# driver_bridge.net
KiCad netlist of a schematic drawn in Altium Designer
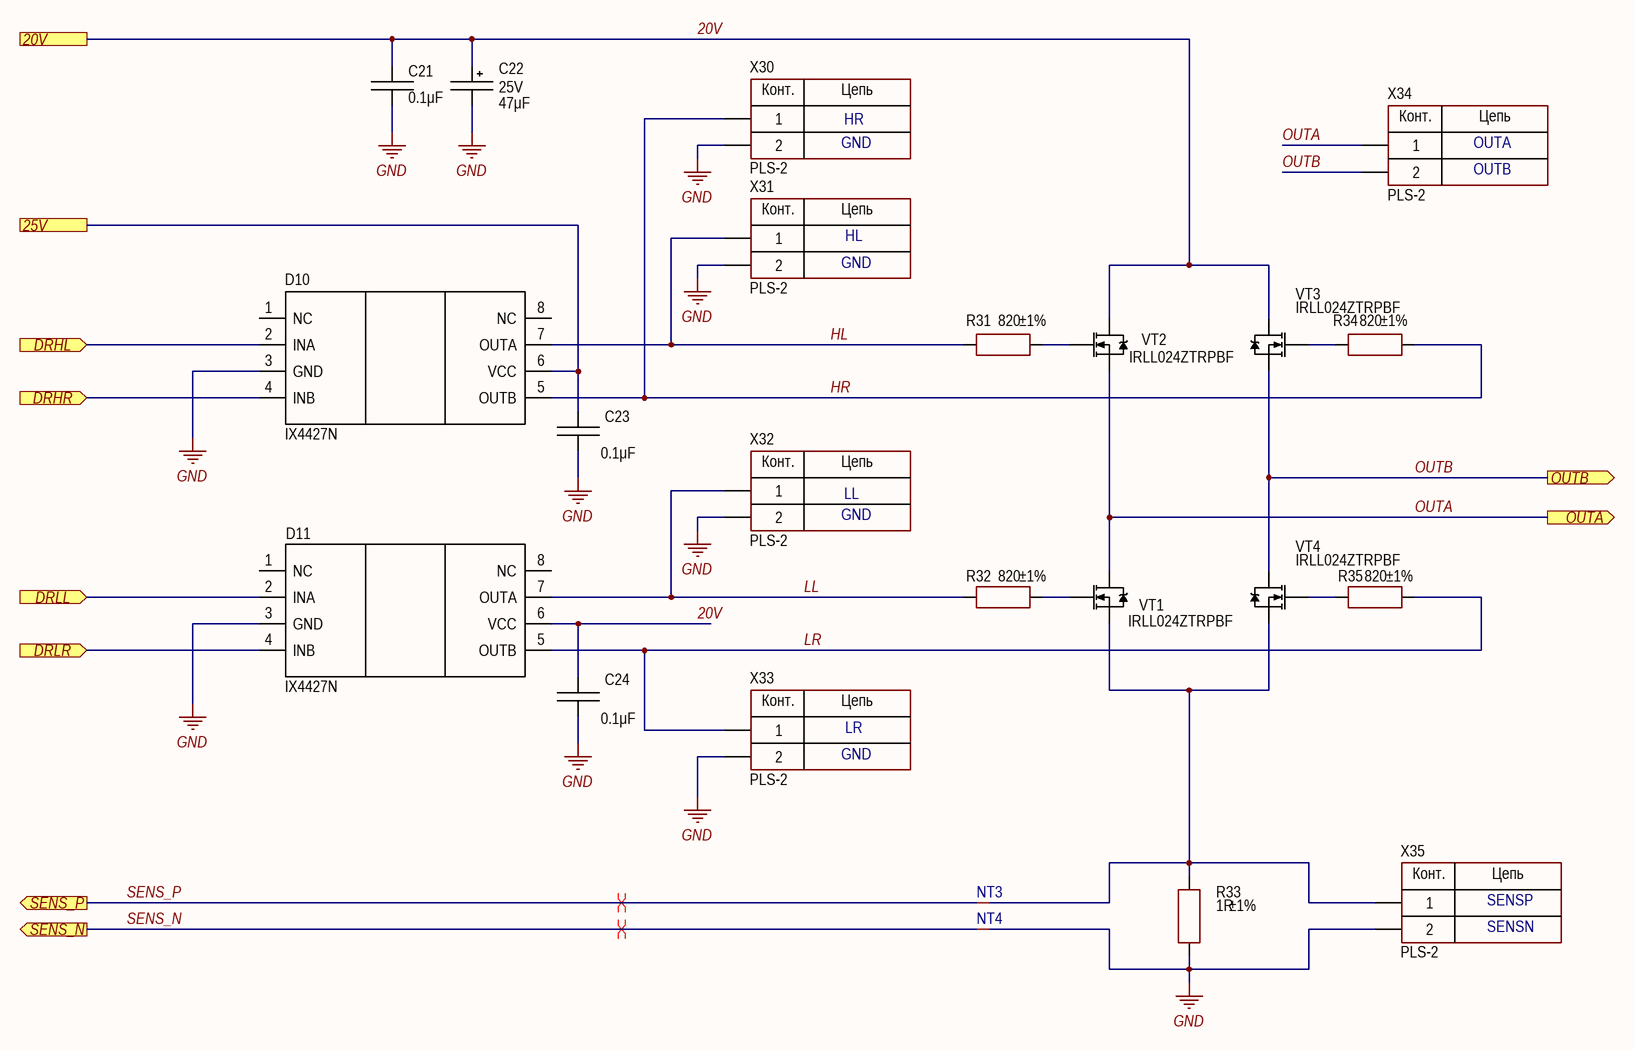
[diagram p0: driver_bridge.SchDoc]

(export (version "E")
  (design (tool "Eeschema 10.0.6"))
  (components
    (comp (ref "C21")
      (value "0.1μF")
      (footprint "CAP: 1206")
      (fields
        (field (name "MANUFACTURER") "Murata Electronics")
        (field (name "PARTNUMBER") "GRM319R71H104K")
        (field (name "VALUEMANUFACTURERPARTNUMBER") "Ceramic capacitor, 0.1μF, X7R, ±10%, 50V, 1206, -55...+125°C")
      )
      (libsource (lib "capacitor") (part "Ceramic_1206"))
    )
    (comp (ref "C22")
      (value "47μF")
      (footprint "CAP: D6.3C2.5H11")
      (fields
        (field (name "MANUFACTURER") "Wurth")
        (field (name "PARTNUMBER") "860080475013")
        (field (name "VALUEMANUFACTURERPARTNUMBER") "Aluminium capacitor, 47μF, 25V, ±20%, 54mOhm, 14x10x5 mm, -55...+105°C")
        (field (name "VOLTAGE") "25V")
      )
      (libsource (lib "capacitor") (part "Aluminium"))
    )
    (comp (ref "C23")
      (value "0.1μF")
      (footprint "CAP: 1206")
      (fields
        (field (name "MANUFACTURER") "Murata Electronics")
        (field (name "PARTNUMBER") "GRM319R71H104K")
        (field (name "VALUEMANUFACTURERPARTNUMBER") "Ceramic capacitor, 0.1μF, X7R, ±10%, 50V, 1206, -55...+125°C")
      )
      (libsource (lib "capacitor") (part "Ceramic_1206"))
    )
    (comp (ref "C24")
      (value "0.1μF")
      (footprint "CAP: 1206")
      (fields
        (field (name "MANUFACTURER") "Murata Electronics")
        (field (name "PARTNUMBER") "GRM319R71H104K")
        (field (name "VALUEMANUFACTURERPARTNUMBER") "Ceramic capacitor, 0.1μF, X7R, ±10%, 50V, 1206, -55...+125°C")
      )
      (libsource (lib "capacitor") (part "Ceramic_1206"))
    )
    (comp (ref "D10")
      (value "Ixys Corporation")
      (footprint "8-SOIC")
      (description "Gate driver")
      (fields (field (name "PARTNUMBER") "IX4427N"))
      (libsource (lib "ic-gate-driver") (part "IX4427N"))
    )
    (comp (ref "D11")
      (value "Ixys Corporation")
      (footprint "8-SOIC")
      (description "Gate driver")
      (fields (field (name "PARTNUMBER") "IX4427N"))
      (libsource (lib "ic-gate-driver") (part "IX4427N"))
    )
    (comp (ref "NT3")
      (value "Net_Tie")
      (footprint "NET TIE 0.5_1.5")
      (libsource (lib "other") (part "Net_Tie"))
    )
    (comp (ref "NT4")
      (value "Net_Tie")
      (footprint "NET TIE 0.5_1.5")
      (libsource (lib "other") (part "Net_Tie"))
    )
    (comp (ref "R31")
      (value "820")
      (footprint "RES: 1206")
      (fields
        (field (name "MANUFACTURER") "Yageo")
        (field (name "PARTNUMBER") "RC1206JR-07100RL")
        (field (name "VALUEMANUFACTURERPARTNUMBER") "Resistor film, 820, ±1%, 1206, 0.25W, -55...+125°C")
        (field (name "TOLERANCE") "±1%")
      )
      (libsource (lib "resistor") (part "Resistor_1206"))
    )
    (comp (ref "R32")
      (value "820")
      (footprint "RES: 1206")
      (fields
        (field (name "MANUFACTURER") "Yageo")
        (field (name "PARTNUMBER") "RC1206JR-07100RL")
        (field (name "VALUEMANUFACTURERPARTNUMBER") "Resistor film, 820, ±1%, 1206, 0.25W, -55...+125°C")
        (field (name "TOLERANCE") "±1%")
      )
      (libsource (lib "resistor") (part "Resistor_1206"))
    )
    (comp (ref "R33")
      (value "1R")
      (footprint "RES: 2512")
      (fields
        (field (name "MANUFACTURER") "Yageo")
        (field (name "PARTNUMBER") "RC2512JK-07100RL")
        (field (name "VALUEMANUFACTURERPARTNUMBER") "Resistor film, 1R, ±1%, 2512, 1W, -55...+125°C")
        (field (name "TOLERANCE") "±1%")
      )
      (libsource (lib "resistor") (part "Resistor_2512"))
    )
    (comp (ref "R34")
      (value "820")
      (footprint "RES: 1206")
      (fields
        (field (name "MANUFACTURER") "Yageo")
        (field (name "PARTNUMBER") "RC1206JR-07100RL")
        (field (name "VALUEMANUFACTURERPARTNUMBER") "Resistor film, 820, ±1%, 1206, 0.25W, -55...+125°C")
        (field (name "TOLERANCE") "±1%")
      )
      (libsource (lib "resistor") (part "Resistor_1206"))
    )
    (comp (ref "R35")
      (value "820")
      (footprint "RES: 1206")
      (fields
        (field (name "MANUFACTURER") "Yageo")
        (field (name "PARTNUMBER") "RC1206JR-07100RL")
        (field (name "VALUEMANUFACTURERPARTNUMBER") "Resistor film, 820, ±1%, 1206, 0.25W, -55...+125°C")
        (field (name "TOLERANCE") "±1%")
      )
      (libsource (lib "resistor") (part "Resistor_1206"))
    )
    (comp (ref "VT1")
      (value "~")
      (footprint "SOT223")
      (fields
        (field (name "MANUFACTURER") "Infineon Technologies")
        (field (name "VALUEMANUFACTURERPARTNUMBER") "MOSFET N-channel transistor, 55V, , 7nC ( Typ.), 1W, 60mOhm, , SOT-223, -55...+150°C")
        (field (name "PARTNUMBER") "IRLL024ZTRPBF")
      )
      (libsource (lib "transistor") (part "MOSFET_N_123"))
    )
    (comp (ref "VT2")
      (value "~")
      (footprint "SOT223")
      (fields
        (field (name "MANUFACTURER") "Infineon Technologies")
        (field (name "VALUEMANUFACTURERPARTNUMBER") "MOSFET N-channel transistor, 55V, , 7nC ( Typ.), 1W, 60mOhm, , SOT-223, -55...+150°C")
        (field (name "PARTNUMBER") "IRLL024ZTRPBF")
      )
      (libsource (lib "transistor") (part "MOSFET_N_123"))
    )
    (comp (ref "VT3")
      (value "~")
      (footprint "SOT223")
      (fields
        (field (name "MANUFACTURER") "Infineon Technologies")
        (field (name "VALUEMANUFACTURERPARTNUMBER") "MOSFET N-channel transistor, 55V, , 7nC ( Typ.), 1W, 60mOhm, , SOT-223, -55...+150°C")
        (field (name "PARTNUMBER") "IRLL024ZTRPBF")
      )
      (libsource (lib "transistor") (part "MOSFET_N_123"))
    )
    (comp (ref "VT4")
      (value "~")
      (footprint "SOT223")
      (fields
        (field (name "MANUFACTURER") "Infineon Technologies")
        (field (name "VALUEMANUFACTURERPARTNUMBER") "MOSFET N-channel transistor, 55V, , 7nC ( Typ.), 1W, 60mOhm, , SOT-223, -55...+150°C")
        (field (name "PARTNUMBER") "IRLL024ZTRPBF")
      )
      (libsource (lib "transistor") (part "MOSFET_N_123"))
    )
    (comp (ref "X30")
      (value "~")
      (footprint "CON: PLS-2")
      (fields
        (field (name "MANUFACTURER") "Connfly")
        (field (name "VALUEMANUFACTURERPARTNUMBER") "Connector, 2pin, 2.54mm, 500VAC, 3A")
        (field (name "PARTNUMBER") "PLS-2")
      )
      (libsource (lib "connector") (part "PLS-2"))
    )
    (comp (ref "X31")
      (value "~")
      (footprint "CON: PLS-2")
      (fields
        (field (name "MANUFACTURER") "Connfly")
        (field (name "VALUEMANUFACTURERPARTNUMBER") "Connector, 2pin, 2.54mm, 500VAC, 3A")
        (field (name "PARTNUMBER") "PLS-2")
      )
      (libsource (lib "connector") (part "PLS-2"))
    )
    (comp (ref "X32")
      (value "~")
      (footprint "CON: PLS-2")
      (fields
        (field (name "MANUFACTURER") "Connfly")
        (field (name "VALUEMANUFACTURERPARTNUMBER") "Connector, 2pin, 2.54mm, 500VAC, 3A")
        (field (name "PARTNUMBER") "PLS-2")
      )
      (libsource (lib "connector") (part "PLS-2"))
    )
    (comp (ref "X33")
      (value "~")
      (footprint "CON: PLS-2")
      (fields
        (field (name "MANUFACTURER") "Connfly")
        (field (name "VALUEMANUFACTURERPARTNUMBER") "Connector, 2pin, 2.54mm, 500VAC, 3A")
        (field (name "PARTNUMBER") "PLS-2")
      )
      (libsource (lib "connector") (part "PLS-2"))
    )
    (comp (ref "X34")
      (value "~")
      (footprint "CON: PLS-2")
      (fields
        (field (name "MANUFACTURER") "Connfly")
        (field (name "VALUEMANUFACTURERPARTNUMBER") "Connector, 2pin, 2.54mm, 500VAC, 3A")
        (field (name "PARTNUMBER") "PLS-2")
      )
      (libsource (lib "connector") (part "PLS-2"))
    )
    (comp (ref "X35")
      (value "~")
      (footprint "CON: PLS-2")
      (fields
        (field (name "MANUFACTURER") "Connfly")
        (field (name "VALUEMANUFACTURERPARTNUMBER") "Connector, 2pin, 2.54mm, 500VAC, 3A")
        (field (name "PARTNUMBER") "PLS-2")
      )
      (libsource (lib "connector") (part "PLS-2"))
    )
  )
  (nets
    (net (code "1") (name "/20V") (class "Default")
      (node (ref "C21") (pin "2") (pinfunction "2_2") (pintype "passive"))
      (node (ref "C22") (pin "1") (pinfunction "1_1") (pintype "passive"))
      (node (ref "C24") (pin "2") (pinfunction "2_2") (pintype "passive"))
      (node (ref "D11") (pin "6") (pinfunction "VCC_6") (pintype "passive"))
      (node (ref "VT2") (pin "2") (pinfunction "D_2") (pintype "passive"))
      (node (ref "VT3") (pin "2") (pinfunction "D_2") (pintype "passive"))
    )
    (net (code "2") (name "/25V") (class "Default")
      (node (ref "C23") (pin "2") (pinfunction "2_2") (pintype "passive"))
      (node (ref "D10") (pin "6") (pinfunction "VCC_6") (pintype "passive"))
    )
    (net (code "3") (name "/DRHL") (class "Default")
      (node (ref "D10") (pin "2") (pinfunction "INA_2") (pintype "passive"))
    )
    (net (code "4") (name "/DRHR") (class "Default")
      (node (ref "D10") (pin "4") (pinfunction "INB_4") (pintype "passive"))
    )
    (net (code "5") (name "/DRLL") (class "Default")
      (node (ref "D11") (pin "2") (pinfunction "INA_2") (pintype "passive"))
    )
    (net (code "6") (name "/DRLR") (class "Default")
      (node (ref "D11") (pin "4") (pinfunction "INB_4") (pintype "passive"))
    )
    (net (code "7") (name "/HL") (class "Default")
      (node (ref "D10") (pin "7") (pinfunction "OUTA_7") (pintype "passive"))
      (node (ref "R31") (pin "1") (pinfunction "1_1") (pintype "passive"))
      (node (ref "X31") (pin "1") (pinfunction "1_1") (pintype "passive"))
    )
    (net (code "8") (name "/HR") (class "Default")
      (node (ref "D10") (pin "5") (pinfunction "OUTB_5") (pintype "passive"))
      (node (ref "R34") (pin "2") (pinfunction "2_2") (pintype "passive"))
      (node (ref "X30") (pin "1") (pinfunction "1_1") (pintype "passive"))
    )
    (net (code "9") (name "/LL") (class "Default")
      (node (ref "D11") (pin "7") (pinfunction "OUTA_7") (pintype "passive"))
      (node (ref "R32") (pin "1") (pinfunction "1_1") (pintype "passive"))
      (node (ref "X32") (pin "1") (pinfunction "1_1") (pintype "passive"))
    )
    (net (code "10") (name "/LR") (class "Default")
      (node (ref "D11") (pin "5") (pinfunction "OUTB_5") (pintype "passive"))
      (node (ref "R35") (pin "2") (pinfunction "2_2") (pintype "passive"))
      (node (ref "X33") (pin "1") (pinfunction "1_1") (pintype "passive"))
    )
    (net (code "11") (name "/OUTA") (class "Default")
      (node (ref "VT1") (pin "2") (pinfunction "D_2") (pintype "passive"))
      (node (ref "VT2") (pin "3") (pinfunction "S_3") (pintype "passive"))
      (node (ref "X34") (pin "1") (pinfunction "1_1") (pintype "passive"))
    )
    (net (code "12") (name "/OUTB") (class "Default")
      (node (ref "VT3") (pin "3") (pinfunction "S_3") (pintype "passive"))
      (node (ref "VT4") (pin "2") (pinfunction "D_2") (pintype "passive"))
      (node (ref "X34") (pin "2") (pinfunction "2_2") (pintype "passive"))
    )
    (net (code "13") (name "/SENS_N") (class "Default")
      (node (ref "NT4") (pin "1") (pinfunction "1_1") (pintype "passive"))
    )
    (net (code "14") (name "/SENS_P") (class "Default")
      (node (ref "NT3") (pin "1") (pinfunction "1_1") (pintype "passive"))
    )
    (net (code "15") (name "GND") (class "Default")
      (node (ref "C21") (pin "1") (pinfunction "1_1") (pintype "passive"))
      (node (ref "C22") (pin "2") (pinfunction "2_2") (pintype "passive"))
      (node (ref "C23") (pin "1") (pinfunction "1_1") (pintype "passive"))
      (node (ref "C24") (pin "1") (pinfunction "1_1") (pintype "passive"))
      (node (ref "D10") (pin "3") (pinfunction "GND_3") (pintype "passive"))
      (node (ref "D11") (pin "3") (pinfunction "GND_3") (pintype "passive"))
      (node (ref "NT4") (pin "2") (pinfunction "2_2") (pintype "passive"))
      (node (ref "R33") (pin "1") (pinfunction "1_1") (pintype "passive"))
      (node (ref "X30") (pin "2") (pinfunction "2_2") (pintype "passive"))
      (node (ref "X31") (pin "2") (pinfunction "2_2") (pintype "passive"))
      (node (ref "X32") (pin "2") (pinfunction "2_2") (pintype "passive"))
      (node (ref "X33") (pin "2") (pinfunction "2_2") (pintype "passive"))
      (node (ref "X35") (pin "2") (pinfunction "2_2") (pintype "passive"))
    )
    (net (code "16") (name "Net-(VT1-G)") (class "Default")
      (node (ref "R32") (pin "2") (pinfunction "2_2") (pintype "passive"))
      (node (ref "VT1") (pin "1") (pinfunction "G_1") (pintype "passive"))
    )
    (net (code "17") (name "Net-(VT1-S)") (class "Default")
      (node (ref "NT3") (pin "2") (pinfunction "2_2") (pintype "passive"))
      (node (ref "R33") (pin "2") (pinfunction "2_2") (pintype "passive"))
      (node (ref "VT1") (pin "3") (pinfunction "S_3") (pintype "passive"))
      (node (ref "VT4") (pin "3") (pinfunction "S_3") (pintype "passive"))
      (node (ref "X35") (pin "1") (pinfunction "1_1") (pintype "passive"))
    )
    (net (code "18") (name "Net-(VT2-G)") (class "Default")
      (node (ref "R31") (pin "2") (pinfunction "2_2") (pintype "passive"))
      (node (ref "VT2") (pin "1") (pinfunction "G_1") (pintype "passive"))
    )
    (net (code "19") (name "Net-(VT3-G)") (class "Default")
      (node (ref "R34") (pin "1") (pinfunction "1_1") (pintype "passive"))
      (node (ref "VT3") (pin "1") (pinfunction "G_1") (pintype "passive"))
    )
    (net (code "20") (name "Net-(VT4-G)") (class "Default")
      (node (ref "R35") (pin "1") (pinfunction "1_1") (pintype "passive"))
      (node (ref "VT4") (pin "1") (pinfunction "G_1") (pintype "passive"))
    )
    (net (code "21") (name "unconnected-(D10-NC-Pad1)") (class "Default")
      (node (ref "D10") (pin "1") (pinfunction "NC_1") (pintype "passive"))
    )
    (net (code "22") (name "unconnected-(D10-NC-Pad8)") (class "Default")
      (node (ref "D10") (pin "8") (pinfunction "NC_8") (pintype "passive"))
    )
    (net (code "23") (name "unconnected-(D11-NC-Pad1)") (class "Default")
      (node (ref "D11") (pin "1") (pinfunction "NC_1") (pintype "passive"))
    )
    (net (code "24") (name "unconnected-(D11-NC-Pad8)") (class "Default")
      (node (ref "D11") (pin "8") (pinfunction "NC_8") (pintype "passive"))
    )
  )
)
